# SP26_brainstim3_VCCS_Schematic_easyEDA_S.net
KiCad netlist of a schematic drawn in EasyEDA
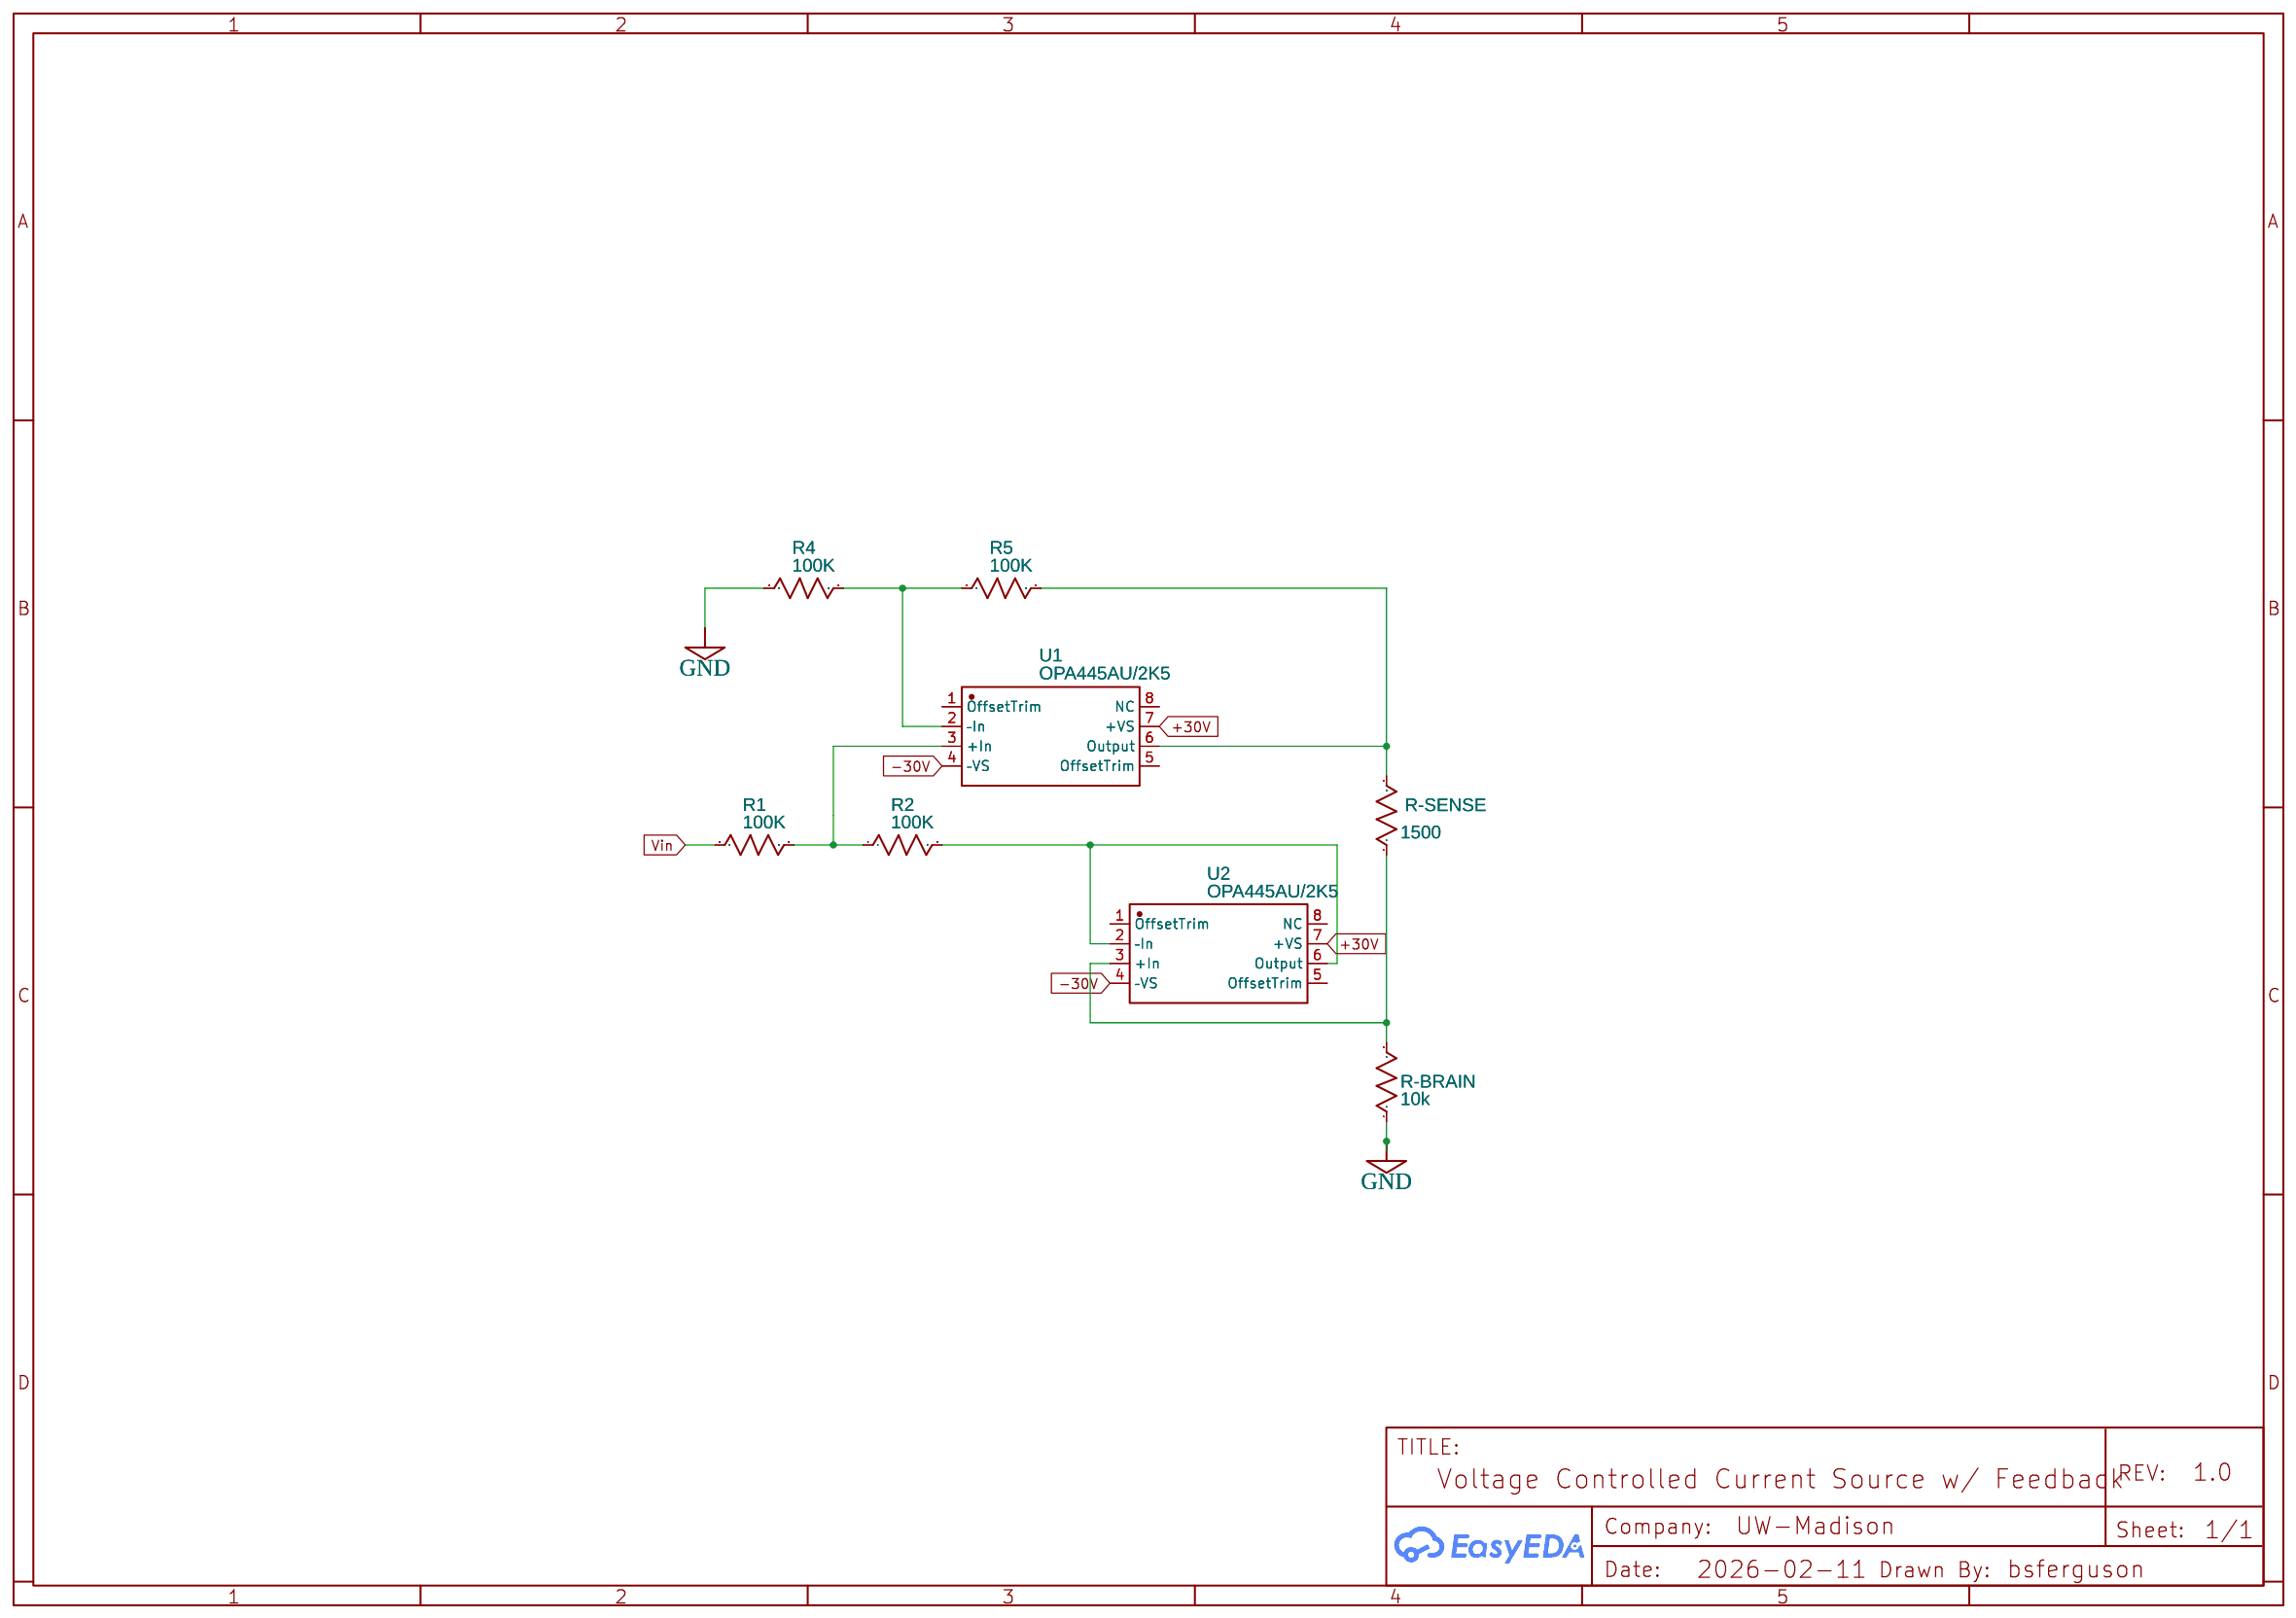
[diagram p0: schematic sheet]

(export (version "E")
  (design (tool "Eeschema 10.0.6"))
  (components
    (comp (ref "R-BRAIN") (value "10k") (libsource (lib "") (part "R_0603_US_2")))
    (comp (ref "R-SENSE") (value "1500") (libsource (lib "") (part "R_0603_US_1")))
    (comp (ref "R1") (value "100K") (libsource (lib "") (part "R_0603_US")))
    (comp (ref "R2") (value "100K") (libsource (lib "") (part "R_0603_US")))
    (comp (ref "R4") (value "100K") (libsource (lib "") (part "R_0603_US")))
    (comp (ref "R5") (value "100K") (libsource (lib "") (part "R_0603_US")))
    (comp (ref "U1")
      (value "OPA445AU/2K5")
      (fields (field (name "Manufacturer") "TI(德州仪器)"))
      (libsource (lib "") (part "OPA445AU/2K5"))
    )
    (comp (ref "U2")
      (value "OPA445AU/2K5")
      (fields (field (name "Manufacturer") "TI(德州仪器)"))
      (libsource (lib "") (part "OPA445AU/2K5"))
    )
  )
  (nets
    (net (code "1") (name "+30V") (class "Default")
      (node (ref "U1") (pin "7") (pinfunction "+VS_7") (pintype "unspecified"))
      (node (ref "U2") (pin "7") (pinfunction "+VS_7") (pintype "unspecified"))
    )
    (net (code "2") (name "-30V") (class "Default")
      (node (ref "U1") (pin "4") (pinfunction "–VS_4") (pintype "unspecified"))
      (node (ref "U2") (pin "4") (pinfunction "–VS_4") (pintype "unspecified"))
    )
    (net (code "3") (name "GND") (class "Default")
      (node (ref "R-BRAIN") (pin "1") (pinfunction "1_1") (pintype "unspecified"))
      (node (ref "R4") (pin "1") (pinfunction "1_1") (pintype "unspecified"))
    )
    (net (code "4") (name "Net-(U1-+In)") (class "Default")
      (node (ref "R1") (pin "2") (pinfunction "2_2") (pintype "unspecified"))
      (node (ref "R2") (pin "1") (pinfunction "1_1") (pintype "unspecified"))
      (node (ref "U1") (pin "3") (pinfunction "+In_3") (pintype "unspecified"))
    )
    (net (code "5") (name "Net-(U1-Output)") (class "Default")
      (node (ref "R-SENSE") (pin "2") (pinfunction "2_2") (pintype "unspecified"))
      (node (ref "R5") (pin "2") (pinfunction "2_2") (pintype "unspecified"))
      (node (ref "U1") (pin "6") (pinfunction "Output_6") (pintype "unspecified"))
    )
    (net (code "6") (name "Net-(U1-–In)") (class "Default")
      (node (ref "R4") (pin "2") (pinfunction "2_2") (pintype "unspecified"))
      (node (ref "R5") (pin "1") (pinfunction "1_1") (pintype "unspecified"))
      (node (ref "U1") (pin "2") (pinfunction "–In_2") (pintype "unspecified"))
    )
    (net (code "7") (name "Net-(U2-+In)") (class "Default")
      (node (ref "R-BRAIN") (pin "2") (pinfunction "2_2") (pintype "unspecified"))
      (node (ref "R-SENSE") (pin "1") (pinfunction "1_1") (pintype "unspecified"))
      (node (ref "U2") (pin "3") (pinfunction "+In_3") (pintype "unspecified"))
    )
    (net (code "8") (name "Net-(U2-Output)") (class "Default")
      (node (ref "R2") (pin "2") (pinfunction "2_2") (pintype "unspecified"))
      (node (ref "U2") (pin "2") (pinfunction "–In_2") (pintype "unspecified"))
      (node (ref "U2") (pin "6") (pinfunction "Output_6") (pintype "unspecified"))
    )
    (net (code "9") (name "Vin") (class "Default")
      (node (ref "R1") (pin "1") (pinfunction "1_1") (pintype "unspecified"))
    )
    (net (code "10") (name "unconnected-(U1-NC-Pad8)") (class "Default")
      (node (ref "U1") (pin "8") (pinfunction "NC_8") (pintype "unspecified"))
    )
    (net (code "11") (name "unconnected-(U1-OffsetTrim-Pad1)") (class "Default")
      (node (ref "U1") (pin "1") (pinfunction "OffsetTrim_1") (pintype "unspecified"))
    )
    (net (code "12") (name "unconnected-(U1-OffsetTrim-Pad5)") (class "Default")
      (node (ref "U1") (pin "5") (pinfunction "OffsetTrim_5") (pintype "unspecified"))
    )
    (net (code "13") (name "unconnected-(U2-NC-Pad8)") (class "Default")
      (node (ref "U2") (pin "8") (pinfunction "NC_8") (pintype "unspecified"))
    )
    (net (code "14") (name "unconnected-(U2-OffsetTrim-Pad1)") (class "Default")
      (node (ref "U2") (pin "1") (pinfunction "OffsetTrim_1") (pintype "unspecified"))
    )
    (net (code "15") (name "unconnected-(U2-OffsetTrim-Pad5)") (class "Default")
      (node (ref "U2") (pin "5") (pinfunction "OffsetTrim_5") (pintype "unspecified"))
    )
  )
)
